# MCU.net
KiCad netlist of a schematic drawn in Altium Designer
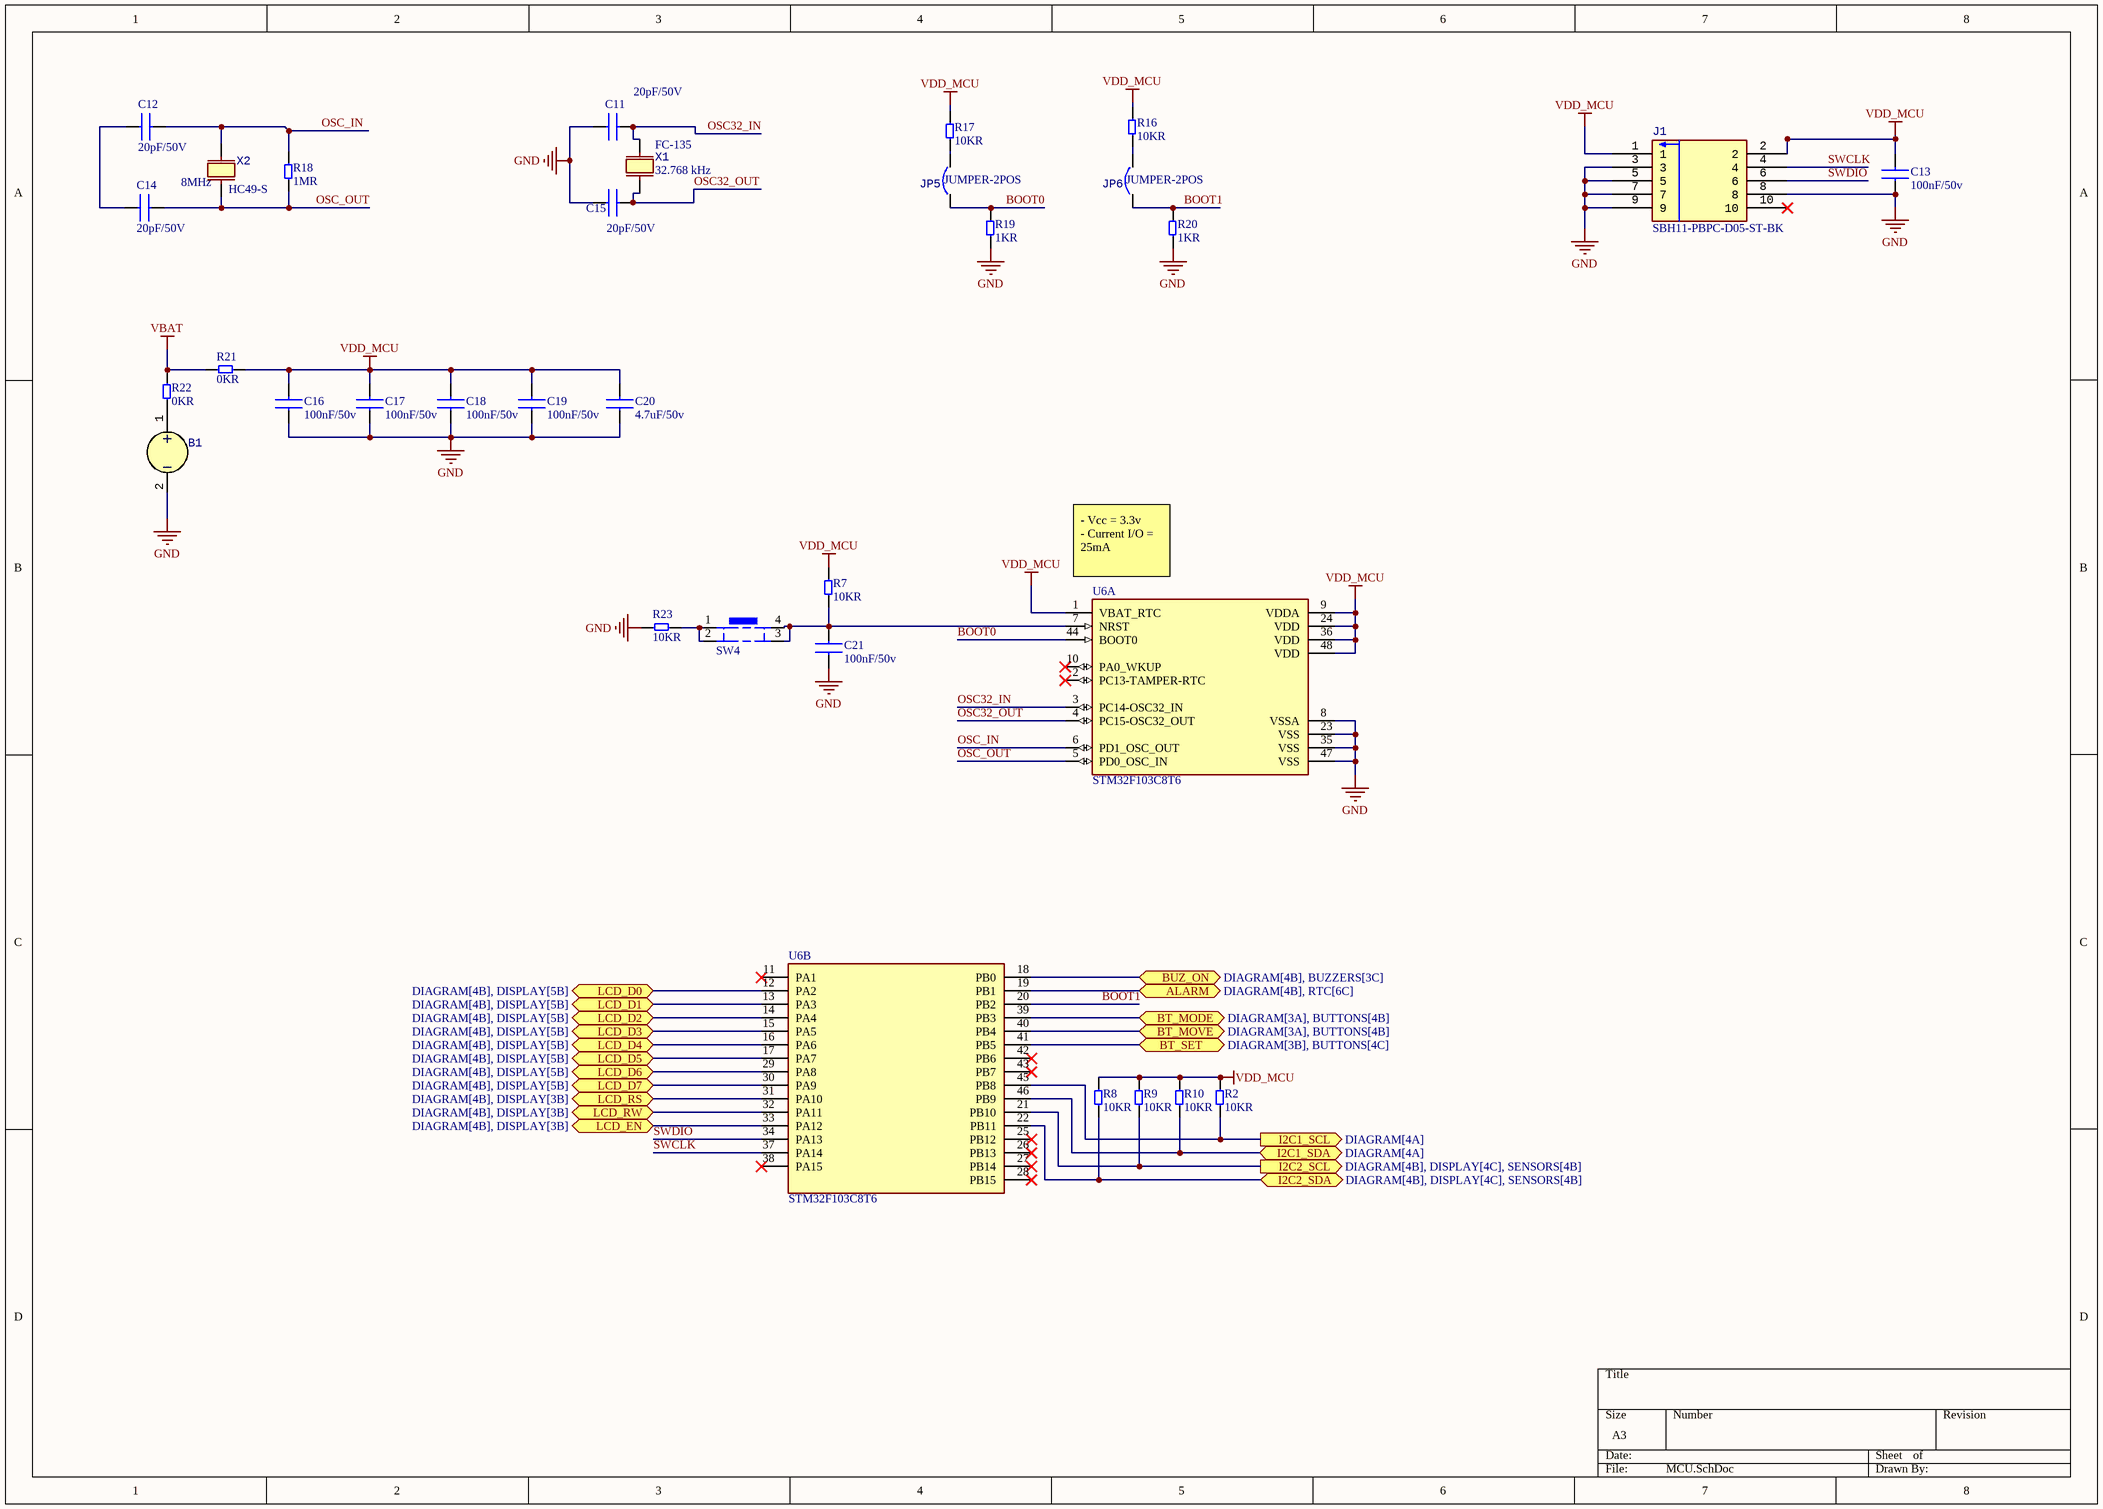
[diagram p0: MCU.SchDoc]

(export (version "E")
  (design (tool "Eeschema 10.0.6"))
  (components
    (comp (ref "B1")
      (value "0")
      (footprint "BAT-HOLD-2032")
      (libsource (lib "Database_Libs1") (part "BATTERY"))
    )
    (comp (ref "C11")
      (value "20pF/50V")
      (footprint "CAP-CER-0805")
      (description "0805 20pF 50V")
      (libsource (lib "Database_Libs1") (part "CAP-CER"))
    )
    (comp (ref "C12")
      (value "20pF/50V")
      (footprint "CAP-CER-0805")
      (description "0805 20pF 50V")
      (libsource (lib "Database_Libs1") (part "CAP-CER"))
    )
    (comp (ref "C13")
      (value "100nF/50v")
      (footprint "CAP-CER-0805")
      (description "Tụ Gốm 0805 100nF (0.1uF) 50V")
      (libsource (lib "Database_Libs1") (part "CAP-CER"))
    )
    (comp (ref "C14")
      (value "20pF/50V")
      (footprint "CAP-CER-0805")
      (description "0805 20pF 50V")
      (libsource (lib "Database_Libs1") (part "CAP-CER"))
    )
    (comp (ref "C15")
      (value "20pF/50V")
      (footprint "CAP-CER-0805")
      (description "0805 20pF 50V")
      (libsource (lib "Database_Libs1") (part "CAP-CER"))
    )
    (comp (ref "C16")
      (value "100nF/50v")
      (footprint "CAP-CER-0805")
      (description "Tụ Gốm 0805 100nF (0.1uF) 50V")
      (libsource (lib "Database_Libs1") (part "CAP-CER"))
    )
    (comp (ref "C17")
      (value "100nF/50v")
      (footprint "CAP-CER-0805")
      (description "Tụ Gốm 0805 100nF (0.1uF) 50V")
      (libsource (lib "Database_Libs1") (part "CAP-CER"))
    )
    (comp (ref "C18")
      (value "100nF/50v")
      (footprint "CAP-CER-0805")
      (description "Tụ Gốm 0805 100nF (0.1uF) 50V")
      (libsource (lib "Database_Libs1") (part "CAP-CER"))
    )
    (comp (ref "C19")
      (value "100nF/50v")
      (footprint "CAP-CER-0805")
      (description "Tụ Gốm 0805 100nF (0.1uF) 50V")
      (libsource (lib "Database_Libs1") (part "CAP-CER"))
    )
    (comp (ref "C20")
      (value "4.7uF/50v")
      (footprint "CAP-CER-0805")
      (description "Tụ Gốm 0805 4.7uF 50V")
      (libsource (lib "Database_Libs1") (part "CAP-CER"))
    )
    (comp (ref "C21")
      (value "100nF/50v")
      (footprint "CAP-CER-0805")
      (description "Tụ Gốm 0805 100nF (0.1uF) 50V")
      (libsource (lib "Database_Libs1") (part "CAP-CER"))
    )
    (comp (ref "J1")
      (value "SBH11-PBPC-D05-ST-BK")
      (footprint "IDC-10POS-2.54")
      (fields (field (name "MFR# #") "SBH11-PBPC-D05-ST-BK"))
      (libsource (lib "Database_Libs1") (part "HEADER-10POS-5X2"))
    )
    (comp (ref "JP5")
      (value "JUMPER-2POS")
      (footprint "JUMPER-2POS-2.54")
      (fields (field (name "MFR# #") "JUMPER-2POS"))
      (libsource (lib "Database_Libs1") (part "JUMPER-2POS"))
    )
    (comp (ref "JP6")
      (value "JUMPER-2POS")
      (footprint "JUMPER-2POS-2.54")
      (fields (field (name "MFR# #") "JUMPER-2POS"))
      (libsource (lib "Database_Libs1") (part "JUMPER-2POS"))
    )
    (comp (ref "R2")
      (value "10KR")
      (footprint "RES-SMD-0805")
      (description "Điện Trở 10 KOhm 0805 1%")
      (libsource (lib "Database_Libs1") (part "RES_SMD"))
    )
    (comp (ref "R7")
      (value "10KR")
      (footprint "RES-SMD-0805")
      (description "Điện Trở 10 KOhm 0805 1%")
      (libsource (lib "Database_Libs1") (part "RES_SMD"))
    )
    (comp (ref "R8")
      (value "10KR")
      (footprint "RES-SMD-0805")
      (description "Điện Trở 10 KOhm 0805 1%")
      (libsource (lib "Database_Libs1") (part "RES_SMD"))
    )
    (comp (ref "R9")
      (value "10KR")
      (footprint "RES-SMD-0805")
      (description "Điện Trở 10 KOhm 0805 1%")
      (libsource (lib "Database_Libs1") (part "RES_SMD"))
    )
    (comp (ref "R10")
      (value "10KR")
      (footprint "RES-SMD-0805")
      (description "Điện Trở 10 KOhm 0805 1%")
      (libsource (lib "Database_Libs1") (part "RES_SMD"))
    )
    (comp (ref "R16")
      (value "10KR")
      (footprint "RES-SMD-0805")
      (description "Điện Trở 10 KOhm 0805 1%")
      (libsource (lib "Database_Libs1") (part "RES_SMD"))
    )
    (comp (ref "R17")
      (value "10KR")
      (footprint "RES-SMD-0805")
      (description "Điện Trở 10 KOhm 0805 1%")
      (libsource (lib "Database_Libs1") (part "RES_SMD"))
    )
    (comp (ref "R18")
      (value "1MR")
      (footprint "RES-SMD-0805")
      (description "Điện Trở 1 MOhm 0805 1%")
      (libsource (lib "Database_Libs1") (part "RES_SMD"))
    )
    (comp (ref "R19")
      (value "1KR")
      (footprint "RES-SMD-0805")
      (description "Điện Trở 1 KOhm 0805 1%")
      (libsource (lib "Database_Libs1") (part "RES_SMD"))
    )
    (comp (ref "R20")
      (value "1KR")
      (footprint "RES-SMD-0805")
      (description "Điện Trở 1 KOhm 0805 1%")
      (libsource (lib "Database_Libs1") (part "RES_SMD"))
    )
    (comp (ref "R21")
      (value "0KR")
      (footprint "RES-SMD-0805")
      (description "Điện Trở 0 Ohm 0805 1%")
      (libsource (lib "Database_Libs1") (part "RES_SMD"))
    )
    (comp (ref "R22")
      (value "0KR")
      (footprint "RES-SMD-0805")
      (description "Điện Trở 0 Ohm 0805 1%")
      (libsource (lib "Database_Libs1") (part "RES_SMD"))
    )
    (comp (ref "R23")
      (value "10KR")
      (footprint "RES-SMD-0805")
      (description "Điện Trở 10 KOhm 0805 1%")
      (libsource (lib "Database_Libs1") (part "RES_SMD"))
    )
    (comp (ref "SW4")
      (value "0")
      (footprint "Tactice-Switch-TH-12x12-4.5mm")
      (description "Nút Nhấn 6x6mm Cao 6mm 4 Chân Xuyên Lỗ")
      (libsource (lib "Database_Libs1") (part "Tactice Switch"))
    )
    (comp (ref "U6")
      (value "STM32F103C8T6")
      (footprint "QFP50P900X900X160-48N")
      (description "ARM® Cortex®-M3 STM32F1 Microcontroller IC 32-Bit 72MHz 64KB (64K x 8) FLASH 48-LQFP (7x7)")
      (fields (field (name "MF") "STMicroelectronics"))
      (libsource (lib "ID") (part "STM32F103C8T6"))
    )
    (comp (ref "X1")
      (value "32.768 kHz")
      (footprint "XTAL_FC-135_32.7680KA-A0")
      (description "Thạch Anh FC-135 32.768KHz 3215")
      (fields (field (name "MFR# #") "FC-135"))
      (libsource (lib "Database_Libs1") (part "CRYSTAL-2POS"))
    )
    (comp (ref "X2")
      (value "8MHz")
      (footprint "HC49-S")
      (description "8 MHz ±30ppm Crystal 18pF 100 Ohms HC-49/US")
      (fields (field (name "MFR# #") "HC49-S"))
      (libsource (lib "Database_Libs1") (part "CRYSTAL-2POS"))
    )
  )
  (nets
    (net (code "1") (name "/ALARM") (class "Default")
      (node (ref "U6") (pin "19") (pinfunction "PB1_19") (pintype "passive"))
    )
    (net (code "2") (name "/BOOT0") (class "Default")
      (node (ref "JP5") (pin "1") (pinfunction "1_1") (pintype "passive"))
      (node (ref "R19") (pin "2") (pinfunction "2_2") (pintype "passive"))
      (node (ref "U6") (pin "44") (pinfunction "BOOT0_44") (pintype "input"))
    )
    (net (code "3") (name "/BOOT1") (class "Default")
      (node (ref "JP6") (pin "1") (pinfunction "1_1") (pintype "passive"))
      (node (ref "R20") (pin "2") (pinfunction "2_2") (pintype "passive"))
      (node (ref "U6") (pin "20") (pinfunction "PB2_20") (pintype "passive"))
    )
    (net (code "4") (name "/BT_MODE") (class "Default")
      (node (ref "U6") (pin "39") (pinfunction "PB3_39") (pintype "passive"))
    )
    (net (code "5") (name "/BT_MOVE") (class "Default")
      (node (ref "U6") (pin "40") (pinfunction "PB4_40") (pintype "passive"))
    )
    (net (code "6") (name "/BT_SET") (class "Default")
      (node (ref "U6") (pin "41") (pinfunction "PB5_41") (pintype "passive"))
    )
    (net (code "7") (name "/BUZ_ON") (class "Default")
      (node (ref "U6") (pin "18") (pinfunction "PB0_18") (pintype "passive"))
    )
    (net (code "8") (name "/I2C1_SCL") (class "Default")
      (node (ref "R2") (pin "1") (pinfunction "1_1") (pintype "passive"))
      (node (ref "U6") (pin "45") (pinfunction "PB8_45") (pintype "passive"))
    )
    (net (code "9") (name "/I2C1_SDA") (class "Default")
      (node (ref "R10") (pin "1") (pinfunction "1_1") (pintype "passive"))
      (node (ref "U6") (pin "46") (pinfunction "PB9_46") (pintype "passive"))
    )
    (net (code "10") (name "/I2C2_SCL") (class "Default")
      (node (ref "R9") (pin "1") (pinfunction "1_1") (pintype "passive"))
      (node (ref "U6") (pin "21") (pinfunction "PB10_21") (pintype "passive"))
    )
    (net (code "11") (name "/I2C2_SDA") (class "Default")
      (node (ref "R8") (pin "1") (pinfunction "1_1") (pintype "passive"))
      (node (ref "U6") (pin "22") (pinfunction "PB11_22") (pintype "passive"))
    )
    (net (code "12") (name "/LCD_D0") (class "Default")
      (node (ref "U6") (pin "12") (pinfunction "PA2_12") (pintype "passive"))
    )
    (net (code "13") (name "/LCD_D1") (class "Default")
      (node (ref "U6") (pin "13") (pinfunction "PA3_13") (pintype "passive"))
    )
    (net (code "14") (name "/LCD_D2") (class "Default")
      (node (ref "U6") (pin "14") (pinfunction "PA4_14") (pintype "passive"))
    )
    (net (code "15") (name "/LCD_D3") (class "Default")
      (node (ref "U6") (pin "15") (pinfunction "PA5_15") (pintype "passive"))
    )
    (net (code "16") (name "/LCD_D4") (class "Default")
      (node (ref "U6") (pin "16") (pinfunction "PA6_16") (pintype "passive"))
    )
    (net (code "17") (name "/LCD_D5") (class "Default")
      (node (ref "U6") (pin "17") (pinfunction "PA7_17") (pintype "passive"))
    )
    (net (code "18") (name "/LCD_D6") (class "Default")
      (node (ref "U6") (pin "29") (pinfunction "PA8_29") (pintype "passive"))
    )
    (net (code "19") (name "/LCD_D7") (class "Default")
      (node (ref "U6") (pin "30") (pinfunction "PA9_30") (pintype "passive"))
    )
    (net (code "20") (name "/LCD_EN") (class "Default")
      (node (ref "U6") (pin "33") (pinfunction "PA12_33") (pintype "passive"))
    )
    (net (code "21") (name "/LCD_RS") (class "Default")
      (node (ref "U6") (pin "31") (pinfunction "PA10_31") (pintype "passive"))
    )
    (net (code "22") (name "/LCD_RW") (class "Default")
      (node (ref "U6") (pin "32") (pinfunction "PA11_32") (pintype "passive"))
    )
    (net (code "23") (name "/OSC32_IN") (class "Default")
      (node (ref "C11") (pin "2") (pinfunction "2_2") (pintype "passive"))
      (node (ref "U6") (pin "3") (pinfunction "PC14-OSC32_IN_3") (pintype "bidirectional"))
      (node (ref "X1") (pin "2") (pinfunction "2_2") (pintype "passive"))
    )
    (net (code "24") (name "/OSC32_OUT") (class "Default")
      (node (ref "C15") (pin "2") (pinfunction "2_2") (pintype "passive"))
      (node (ref "U6") (pin "4") (pinfunction "PC15-OSC32_OUT_4") (pintype "bidirectional"))
      (node (ref "X1") (pin "1") (pinfunction "1_1") (pintype "passive"))
    )
    (net (code "25") (name "/OSC_IN") (class "Default")
      (node (ref "C12") (pin "2") (pinfunction "2_2") (pintype "passive"))
      (node (ref "R18") (pin "2") (pinfunction "2_2") (pintype "passive"))
      (node (ref "U6") (pin "6") (pinfunction "PD1_OSC_OUT_6") (pintype "bidirectional"))
      (node (ref "X2") (pin "2") (pinfunction "2_2") (pintype "passive"))
    )
    (net (code "26") (name "/OSC_OUT") (class "Default")
      (node (ref "C14") (pin "2") (pinfunction "2_2") (pintype "passive"))
      (node (ref "R18") (pin "1") (pinfunction "1_1") (pintype "passive"))
      (node (ref "U6") (pin "5") (pinfunction "PD0_OSC_IN_5") (pintype "bidirectional"))
      (node (ref "X2") (pin "1") (pinfunction "1_1") (pintype "passive"))
    )
    (net (code "27") (name "/SWCLK") (class "Default")
      (node (ref "J1") (pin "4") (pinfunction "4_4") (pintype "passive"))
      (node (ref "U6") (pin "37") (pinfunction "PA14_37") (pintype "passive"))
    )
    (net (code "28") (name "/SWDIO") (class "Default")
      (node (ref "J1") (pin "6") (pinfunction "6_6") (pintype "passive"))
      (node (ref "U6") (pin "34") (pinfunction "PA13_34") (pintype "passive"))
    )
    (net (code "29") (name "GND") (class "Default")
      (node (ref "B1") (pin "2") (pinfunction "-_2") (pintype "passive"))
      (node (ref "C11") (pin "1") (pinfunction "1_1") (pintype "passive"))
      (node (ref "C13") (pin "1") (pinfunction "1_1") (pintype "passive"))
      (node (ref "C15") (pin "1") (pinfunction "1_1") (pintype "passive"))
      (node (ref "C16") (pin "1") (pinfunction "1_1") (pintype "passive"))
      (node (ref "C17") (pin "1") (pinfunction "1_1") (pintype "passive"))
      (node (ref "C18") (pin "1") (pinfunction "1_1") (pintype "passive"))
      (node (ref "C19") (pin "1") (pinfunction "1_1") (pintype "passive"))
      (node (ref "C20") (pin "1") (pinfunction "1_1") (pintype "passive"))
      (node (ref "C21") (pin "2") (pinfunction "2_2") (pintype "passive"))
      (node (ref "J1") (pin "3") (pinfunction "3_3") (pintype "passive"))
      (node (ref "J1") (pin "5") (pinfunction "5_5") (pintype "passive"))
      (node (ref "J1") (pin "7") (pinfunction "7_7") (pintype "passive"))
      (node (ref "J1") (pin "8") (pinfunction "8_8") (pintype "passive"))
      (node (ref "J1") (pin "9") (pinfunction "9_9") (pintype "passive"))
      (node (ref "R19") (pin "1") (pinfunction "1_1") (pintype "passive"))
      (node (ref "R20") (pin "1") (pinfunction "1_1") (pintype "passive"))
      (node (ref "R23") (pin "1") (pinfunction "1_1") (pintype "passive"))
      (node (ref "U6") (pin "23") (pinfunction "VSS_23") (pintype "power_in"))
      (node (ref "U6") (pin "35") (pinfunction "VSS_35") (pintype "power_in"))
      (node (ref "U6") (pin "47") (pinfunction "VSS_47") (pintype "power_in"))
      (node (ref "U6") (pin "8") (pinfunction "VSSA_8") (pintype "power_in"))
    )
    (net (code "30") (name "Net-(B1-+)") (class "Default")
      (node (ref "B1") (pin "1") (pinfunction "+_1") (pintype "passive"))
      (node (ref "R22") (pin "1") (pinfunction "1_1") (pintype "passive"))
    )
    (net (code "31") (name "Net-(C12-Pad1)") (class "Default")
      (node (ref "C12") (pin "1") (pinfunction "1_1") (pintype "passive"))
      (node (ref "C14") (pin "1") (pinfunction "1_1") (pintype "passive"))
    )
    (net (code "32") (name "Net-(JP5-Pad2)") (class "Default")
      (node (ref "JP5") (pin "2") (pinfunction "2_2") (pintype "passive"))
      (node (ref "R17") (pin "1") (pinfunction "1_1") (pintype "passive"))
    )
    (net (code "33") (name "Net-(JP6-Pad2)") (class "Default")
      (node (ref "JP6") (pin "2") (pinfunction "2_2") (pintype "passive"))
      (node (ref "R16") (pin "1") (pinfunction "1_1") (pintype "passive"))
    )
    (net (code "34") (name "Net-(R23-Pad2)") (class "Default")
      (node (ref "R23") (pin "2") (pinfunction "2_2") (pintype "passive"))
      (node (ref "SW4") (pin "1") (pinfunction "1_1") (pintype "passive"))
      (node (ref "SW4") (pin "2") (pinfunction "2_2") (pintype "passive"))
    )
    (net (code "35") (name "Net-(U6A-NRST)") (class "Default")
      (node (ref "C21") (pin "1") (pinfunction "1_1") (pintype "passive"))
      (node (ref "R7") (pin "1") (pinfunction "1_1") (pintype "passive"))
      (node (ref "SW4") (pin "3") (pinfunction "3_3") (pintype "passive"))
      (node (ref "SW4") (pin "4") (pinfunction "4_4") (pintype "passive"))
      (node (ref "U6") (pin "7") (pinfunction "NRST_7") (pintype "input"))
    )
    (net (code "36") (name "VBAT") (class "Default")
      (node (ref "R21") (pin "1") (pinfunction "1_1") (pintype "passive"))
      (node (ref "R22") (pin "2") (pinfunction "2_2") (pintype "passive"))
    )
    (net (code "37") (name "VDD_MCU") (class "Default")
      (node (ref "C13") (pin "2") (pinfunction "2_2") (pintype "passive"))
      (node (ref "C16") (pin "2") (pinfunction "2_2") (pintype "passive"))
      (node (ref "C17") (pin "2") (pinfunction "2_2") (pintype "passive"))
      (node (ref "C18") (pin "2") (pinfunction "2_2") (pintype "passive"))
      (node (ref "C19") (pin "2") (pinfunction "2_2") (pintype "passive"))
      (node (ref "C20") (pin "2") (pinfunction "2_2") (pintype "passive"))
      (node (ref "J1") (pin "1") (pinfunction "1_1") (pintype "passive"))
      (node (ref "J1") (pin "2") (pinfunction "2_2") (pintype "passive"))
      (node (ref "R10") (pin "2") (pinfunction "2_2") (pintype "passive"))
      (node (ref "R16") (pin "2") (pinfunction "2_2") (pintype "passive"))
      (node (ref "R17") (pin "2") (pinfunction "2_2") (pintype "passive"))
      (node (ref "R2") (pin "2") (pinfunction "2_2") (pintype "passive"))
      (node (ref "R21") (pin "2") (pinfunction "2_2") (pintype "passive"))
      (node (ref "R7") (pin "2") (pinfunction "2_2") (pintype "passive"))
      (node (ref "R8") (pin "2") (pinfunction "2_2") (pintype "passive"))
      (node (ref "R9") (pin "2") (pinfunction "2_2") (pintype "passive"))
      (node (ref "U6") (pin "1") (pinfunction "VBAT_RTC_1") (pintype "power_in"))
      (node (ref "U6") (pin "24") (pinfunction "VDD_24") (pintype "power_in"))
      (node (ref "U6") (pin "36") (pinfunction "VDD_36") (pintype "power_in"))
      (node (ref "U6") (pin "48") (pinfunction "VDD_48") (pintype "power_in"))
      (node (ref "U6") (pin "9") (pinfunction "VDDA_9") (pintype "power_in"))
    )
    (net (code "38") (name "unconnected-(J1-Pad10)") (class "Default")
      (node (ref "J1") (pin "10") (pinfunction "10_10") (pintype "passive+no_connect"))
    )
    (net (code "39") (name "unconnected-(U6A-PA0_WKUP-Pad10)") (class "Default")
      (node (ref "U6") (pin "10") (pinfunction "PA0_WKUP_10") (pintype "bidirectional+no_connect"))
    )
    (net (code "40") (name "unconnected-(U6A-PC13-TAMPER-RTC-Pad2)") (class "Default")
      (node (ref "U6") (pin "2") (pinfunction "PC13-TAMPER-RTC_2") (pintype "bidirectional+no_connect"))
    )
    (net (code "41") (name "unconnected-(U6B-PA1-Pad11)") (class "Default")
      (node (ref "U6") (pin "11") (pinfunction "PA1_11") (pintype "passive+no_connect"))
    )
    (net (code "42") (name "unconnected-(U6B-PA15-Pad38)") (class "Default")
      (node (ref "U6") (pin "38") (pinfunction "PA15_38") (pintype "passive+no_connect"))
    )
    (net (code "43") (name "unconnected-(U6B-PB6-Pad42)") (class "Default")
      (node (ref "U6") (pin "42") (pinfunction "PB6_42") (pintype "passive+no_connect"))
    )
    (net (code "44") (name "unconnected-(U6B-PB7-Pad43)") (class "Default")
      (node (ref "U6") (pin "43") (pinfunction "PB7_43") (pintype "passive+no_connect"))
    )
    (net (code "45") (name "unconnected-(U6B-PB12-Pad25)") (class "Default")
      (node (ref "U6") (pin "25") (pinfunction "PB12_25") (pintype "passive+no_connect"))
    )
    (net (code "46") (name "unconnected-(U6B-PB13-Pad26)") (class "Default")
      (node (ref "U6") (pin "26") (pinfunction "PB13_26") (pintype "passive+no_connect"))
    )
    (net (code "47") (name "unconnected-(U6B-PB14-Pad27)") (class "Default")
      (node (ref "U6") (pin "27") (pinfunction "PB14_27") (pintype "passive+no_connect"))
    )
    (net (code "48") (name "unconnected-(U6B-PB15-Pad28)") (class "Default")
      (node (ref "U6") (pin "28") (pinfunction "PB15_28") (pintype "passive+no_connect"))
    )
  )
)
